# AD5933.net
KiCad netlist of a schematic drawn in EasyEDA Pro
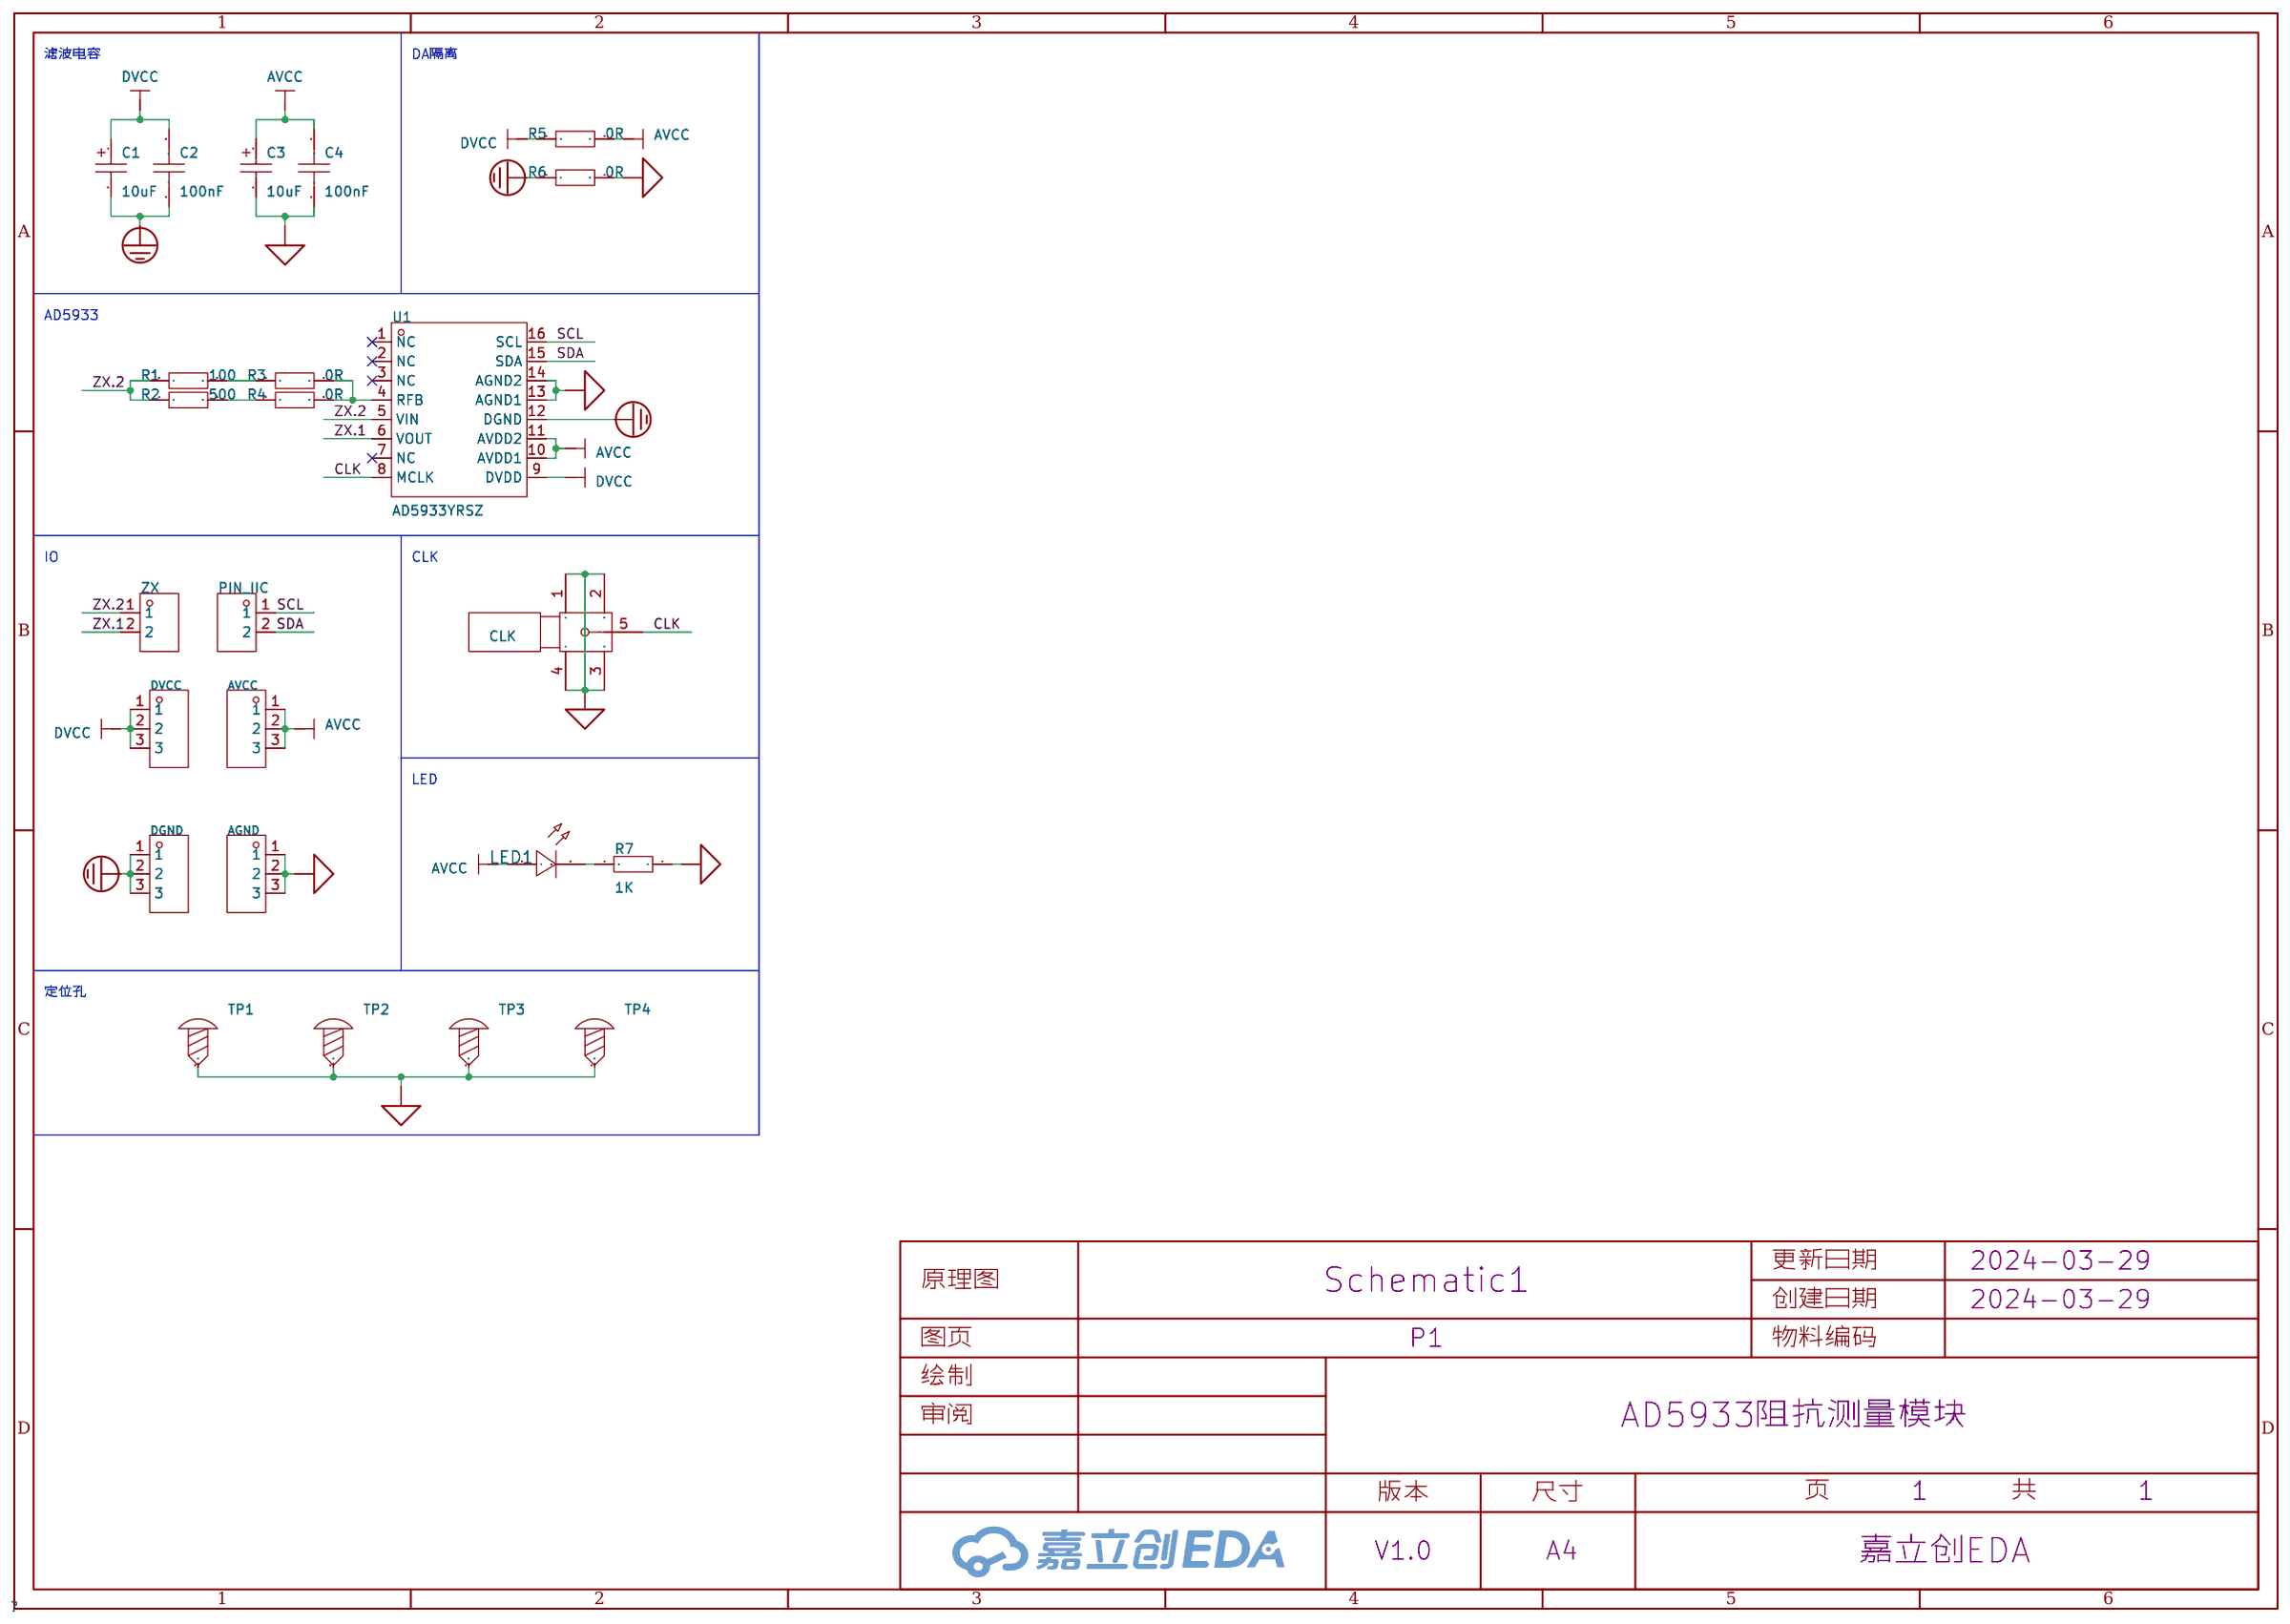
[diagram p0: schematic sheet]

(export (version "E")
  (design (tool "Eeschema 10.0.6"))
  (components
    (comp (ref "AGND")
      (value "~")
      (footprint "easyedapro:HDR-TH_3P-P2.54-V-F")
      (libsource (lib "easyedapro") (part "PM254V-11-03-H85"))
    )
    (comp (ref "AVCC")
      (value "~")
      (footprint "easyedapro:HDR-TH_3P-P2.54-V-F")
      (libsource (lib "easyedapro") (part "PM254V-11-03-H85"))
    )
    (comp (ref "C1")
      (value "10uF")
      (footprint "easyedapro:CAP-SMD_L3.2-W1.6-RD-C7171")
      (description "容值:10uF;精度:±10%;额定电压:16V;等效串联电阻:3Ω@100kHz;")
      (fields (field (name "Manufacturer Part") "TAJA106K016RNJ") (field (name "Manufacturer") "Kyocera AVX"))
      (libsource (lib "easyedapro") (part "TAJA106K016RNJ"))
    )
    (comp (ref "C2")
      (value "100nF")
      (footprint "easyedapro:C0603")
      (libsource (lib "easyedapro") (part "CapAcitance"))
    )
    (comp (ref "C3")
      (value "10uF")
      (footprint "easyedapro:CAP-SMD_L3.2-W1.6-RD-C7171")
      (description "容值:10uF;精度:±10%;额定电压:16V;等效串联电阻:3Ω@100kHz;")
      (fields (field (name "Manufacturer Part") "TAJA106K016RNJ") (field (name "Manufacturer") "Kyocera AVX"))
      (libsource (lib "easyedapro") (part "TAJA106K016RNJ"))
    )
    (comp (ref "C4")
      (value "100nF")
      (footprint "easyedapro:C0603")
      (libsource (lib "easyedapro") (part "CapAcitance"))
    )
    (comp (ref "CLK")
      (value "BWSMA-KE-Z001")
      (footprint "easyedapro:SMA-TH_BWSMA-KE-Z001")
      (fields (field (name "Manufacturer") "BAT WIRELESS(蝙蝠无线)"))
      (libsource (lib "easyedapro") (part "BWSMA-KE-Z001"))
    )
    (comp (ref "DGND")
      (value "~")
      (footprint "easyedapro:HDR-TH_3P-P2.54-V-F")
      (libsource (lib "easyedapro") (part "PM254V-11-03-H85"))
    )
    (comp (ref "DVCC")
      (value "~")
      (footprint "easyedapro:HDR-TH_3P-P2.54-V-F")
      (libsource (lib "easyedapro") (part "PM254V-11-03-H85"))
    )
    (comp (ref "LED1")
      (value "~")
      (footprint "easyedapro:LED_0603")
      (libsource (lib "easyedapro") (part "LED_R"))
    )
    (comp (ref "PIN_IIC")
      (value "ZX-XH2.54-2PZZ")
      (footprint "easyedapro:CONN-TH_2P-P2.50_HX25003-2A")
      (fields (field (name "Manufacturer") "Megastar(兆星)"))
      (libsource (lib "easyedapro") (part "ZX-XH2.54-2PZZ"))
    )
    (comp (ref "R1") (value "100") (footprint "easyedapro:R0603") (libsource (lib "easyedapro") (part "电阻")))
    (comp (ref "R2") (value "500") (footprint "easyedapro:R0603") (libsource (lib "easyedapro") (part "电阻")))
    (comp (ref "R3") (value "0R") (footprint "easyedapro:R0603") (libsource (lib "easyedapro") (part "电阻")))
    (comp (ref "R4") (value "0R") (footprint "easyedapro:R0603") (libsource (lib "easyedapro") (part "电阻")))
    (comp (ref "R5") (value "0R") (footprint "easyedapro:R0603") (libsource (lib "easyedapro") (part "电阻")))
    (comp (ref "R6") (value "0R") (footprint "easyedapro:R0603") (libsource (lib "easyedapro") (part "电阻")))
    (comp (ref "R7") (value "1K") (footprint "easyedapro:R0603") (libsource (lib "easyedapro") (part "电阻")))
    (comp (ref "TP1") (value "~") (footprint "easyedapro:M3螺丝") (libsource (lib "easyedapro") (part "螺丝孔")))
    (comp (ref "TP2") (value "~") (footprint "easyedapro:M3螺丝") (libsource (lib "easyedapro") (part "螺丝孔")))
    (comp (ref "TP3") (value "~") (footprint "easyedapro:M3螺丝") (libsource (lib "easyedapro") (part "螺丝孔")))
    (comp (ref "TP4") (value "~") (footprint "easyedapro:M3螺丝") (libsource (lib "easyedapro") (part "螺丝孔")))
    (comp (ref "U1")
      (value "AD5933YRSZ")
      (footprint "easyedapro:SSOP-16_L6.2-W5.3-P0.65-LS7.8-BL")
      (description "自宽调谐(最大值):-;")
      (fields (field (name "Manufacturer") "ADI(亚德诺)"))
      (libsource (lib "easyedapro") (part "AD5933YRSZ_C578324"))
    )
    (comp (ref "ZX")
      (value "DB301V-3.5-2P-GN-S")
      (footprint "easyedapro:CONN-TH_DB301V-3.5-2P-GN")
      (fields (field (name "Manufacturer") "DORABO(地博电气)"))
      (libsource (lib "easyedapro") (part "DB301V-3.5-2P-GN"))
    )
  )
  (nets
    (net (code "1") (name "/CLK") (class "Default")
      (node (ref "CLK") (pin "5") (pinfunction "5_5") (pintype "unspecified"))
      (node (ref "U1") (pin "8") (pinfunction "MCLK_8") (pintype "unspecified"))
    )
    (net (code "2") (name "/SCL") (class "Default")
      (node (ref "PIN_IIC") (pin "1") (pinfunction "1_1") (pintype "unspecified"))
      (node (ref "U1") (pin "16") (pinfunction "SCL_16") (pintype "unspecified"))
    )
    (net (code "3") (name "/SDA") (class "Default")
      (node (ref "PIN_IIC") (pin "2") (pinfunction "2_2") (pintype "unspecified"))
      (node (ref "U1") (pin "15") (pinfunction "SDA_15") (pintype "unspecified"))
    )
    (net (code "4") (name "/ZX.1") (class "Default")
      (node (ref "U1") (pin "6") (pinfunction "VOUT_6") (pintype "unspecified"))
      (node (ref "ZX") (pin "2") (pinfunction "2_2") (pintype "unspecified"))
    )
    (net (code "5") (name "/ZX.2") (class "Default")
      (node (ref "R1") (pin "1") (pinfunction "1_1") (pintype "input"))
      (node (ref "R2") (pin "1") (pinfunction "1_1") (pintype "input"))
      (node (ref "U1") (pin "5") (pinfunction "VIN_5") (pintype "unspecified"))
      (node (ref "ZX") (pin "1") (pinfunction "1_1") (pintype "unspecified"))
    )
    (net (code "6") (name "AGND") (class "Default")
      (node (ref "AGND") (pin "1") (pinfunction "1_1") (pintype "input"))
      (node (ref "AGND") (pin "2") (pinfunction "2_2") (pintype "input"))
      (node (ref "AGND") (pin "3") (pinfunction "3_3") (pintype "input"))
      (node (ref "C3") (pin "2") (pinfunction "2_2") (pintype "input"))
      (node (ref "C4") (pin "1") (pinfunction "1_1") (pintype "input"))
      (node (ref "CLK") (pin "1") (pinfunction "1_1") (pintype "unspecified"))
      (node (ref "CLK") (pin "2") (pinfunction "2_2") (pintype "unspecified"))
      (node (ref "CLK") (pin "3") (pinfunction "3_3") (pintype "unspecified"))
      (node (ref "CLK") (pin "4") (pinfunction "4_4") (pintype "unspecified"))
      (node (ref "R6") (pin "2") (pinfunction "2_2") (pintype "input"))
      (node (ref "R7") (pin "1") (pinfunction "1_1") (pintype "input"))
      (node (ref "TP1") (pin "1") (pinfunction "1_1") (pintype "input"))
      (node (ref "TP2") (pin "1") (pinfunction "1_1") (pintype "input"))
      (node (ref "TP3") (pin "1") (pinfunction "1_1") (pintype "input"))
      (node (ref "TP4") (pin "1") (pinfunction "1_1") (pintype "input"))
      (node (ref "U1") (pin "13") (pinfunction "AGND1_13") (pintype "unspecified"))
      (node (ref "U1") (pin "14") (pinfunction "AGND2_14") (pintype "unspecified"))
    )
    (net (code "7") (name "AVCC") (class "Default")
      (node (ref "AVCC") (pin "1") (pinfunction "1_1") (pintype "input"))
      (node (ref "AVCC") (pin "2") (pinfunction "2_2") (pintype "input"))
      (node (ref "AVCC") (pin "3") (pinfunction "3_3") (pintype "input"))
      (node (ref "C3") (pin "1") (pinfunction "1_1") (pintype "input"))
      (node (ref "C4") (pin "2") (pinfunction "2_2") (pintype "input"))
      (node (ref "LED1") (pin "2") (pinfunction "A_2") (pintype "input"))
      (node (ref "R5") (pin "2") (pinfunction "2_2") (pintype "input"))
      (node (ref "U1") (pin "10") (pinfunction "AVDD1_10") (pintype "unspecified"))
      (node (ref "U1") (pin "11") (pinfunction "AVDD2_11") (pintype "unspecified"))
    )
    (net (code "8") (name "DVCC") (class "Default")
      (node (ref "C1") (pin "1") (pinfunction "1_1") (pintype "input"))
      (node (ref "C2") (pin "2") (pinfunction "2_2") (pintype "input"))
      (node (ref "DVCC") (pin "1") (pinfunction "1_1") (pintype "input"))
      (node (ref "DVCC") (pin "2") (pinfunction "2_2") (pintype "input"))
      (node (ref "DVCC") (pin "3") (pinfunction "3_3") (pintype "input"))
      (node (ref "R5") (pin "1") (pinfunction "1_1") (pintype "input"))
      (node (ref "U1") (pin "9") (pinfunction "DVDD_9") (pintype "unspecified"))
    )
    (net (code "9") (name "Net-(LED1-C)") (class "Default")
      (node (ref "LED1") (pin "1") (pinfunction "C_1") (pintype "input"))
      (node (ref "R7") (pin "2") (pinfunction "2_2") (pintype "input"))
    )
    (net (code "10") (name "Net-(R1-Pad2)") (class "Default")
      (node (ref "R1") (pin "2") (pinfunction "2_2") (pintype "input"))
      (node (ref "R3") (pin "1") (pinfunction "1_1") (pintype "input"))
    )
    (net (code "11") (name "Net-(R2-Pad2)") (class "Default")
      (node (ref "R2") (pin "2") (pinfunction "2_2") (pintype "input"))
      (node (ref "R4") (pin "1") (pinfunction "1_1") (pintype "input"))
    )
    (net (code "12") (name "Net-(U1-RFB)") (class "Default")
      (node (ref "R3") (pin "2") (pinfunction "2_2") (pintype "input"))
      (node (ref "R4") (pin "2") (pinfunction "2_2") (pintype "input"))
      (node (ref "U1") (pin "4") (pinfunction "RFB_4") (pintype "unspecified"))
    )
    (net (code "13") (name "PGND") (class "Default")
      (node (ref "C1") (pin "2") (pinfunction "2_2") (pintype "input"))
      (node (ref "C2") (pin "1") (pinfunction "1_1") (pintype "input"))
      (node (ref "DGND") (pin "1") (pinfunction "1_1") (pintype "input"))
      (node (ref "DGND") (pin "2") (pinfunction "2_2") (pintype "input"))
      (node (ref "DGND") (pin "3") (pinfunction "3_3") (pintype "input"))
      (node (ref "R6") (pin "1") (pinfunction "1_1") (pintype "input"))
      (node (ref "U1") (pin "12") (pinfunction "DGND_12") (pintype "unspecified"))
    )
    (net (code "14") (name "unconnected-(U1-NC-Pad1)") (class "Default")
      (node (ref "U1") (pin "1") (pinfunction "NC_1") (pintype "unspecified+no_connect"))
    )
    (net (code "15") (name "unconnected-(U1-NC-Pad2)") (class "Default")
      (node (ref "U1") (pin "2") (pinfunction "NC_2") (pintype "unspecified+no_connect"))
    )
    (net (code "16") (name "unconnected-(U1-NC-Pad3)") (class "Default")
      (node (ref "U1") (pin "3") (pinfunction "NC_3") (pintype "unspecified+no_connect"))
    )
    (net (code "17") (name "unconnected-(U1-NC-Pad7)") (class "Default")
      (node (ref "U1") (pin "7") (pinfunction "NC_7") (pintype "unspecified+no_connect"))
    )
  )
)
